# pcb_univ_3-8-0-x-rev3.net
KiCad netlist of a schematic drawn in EAGLE
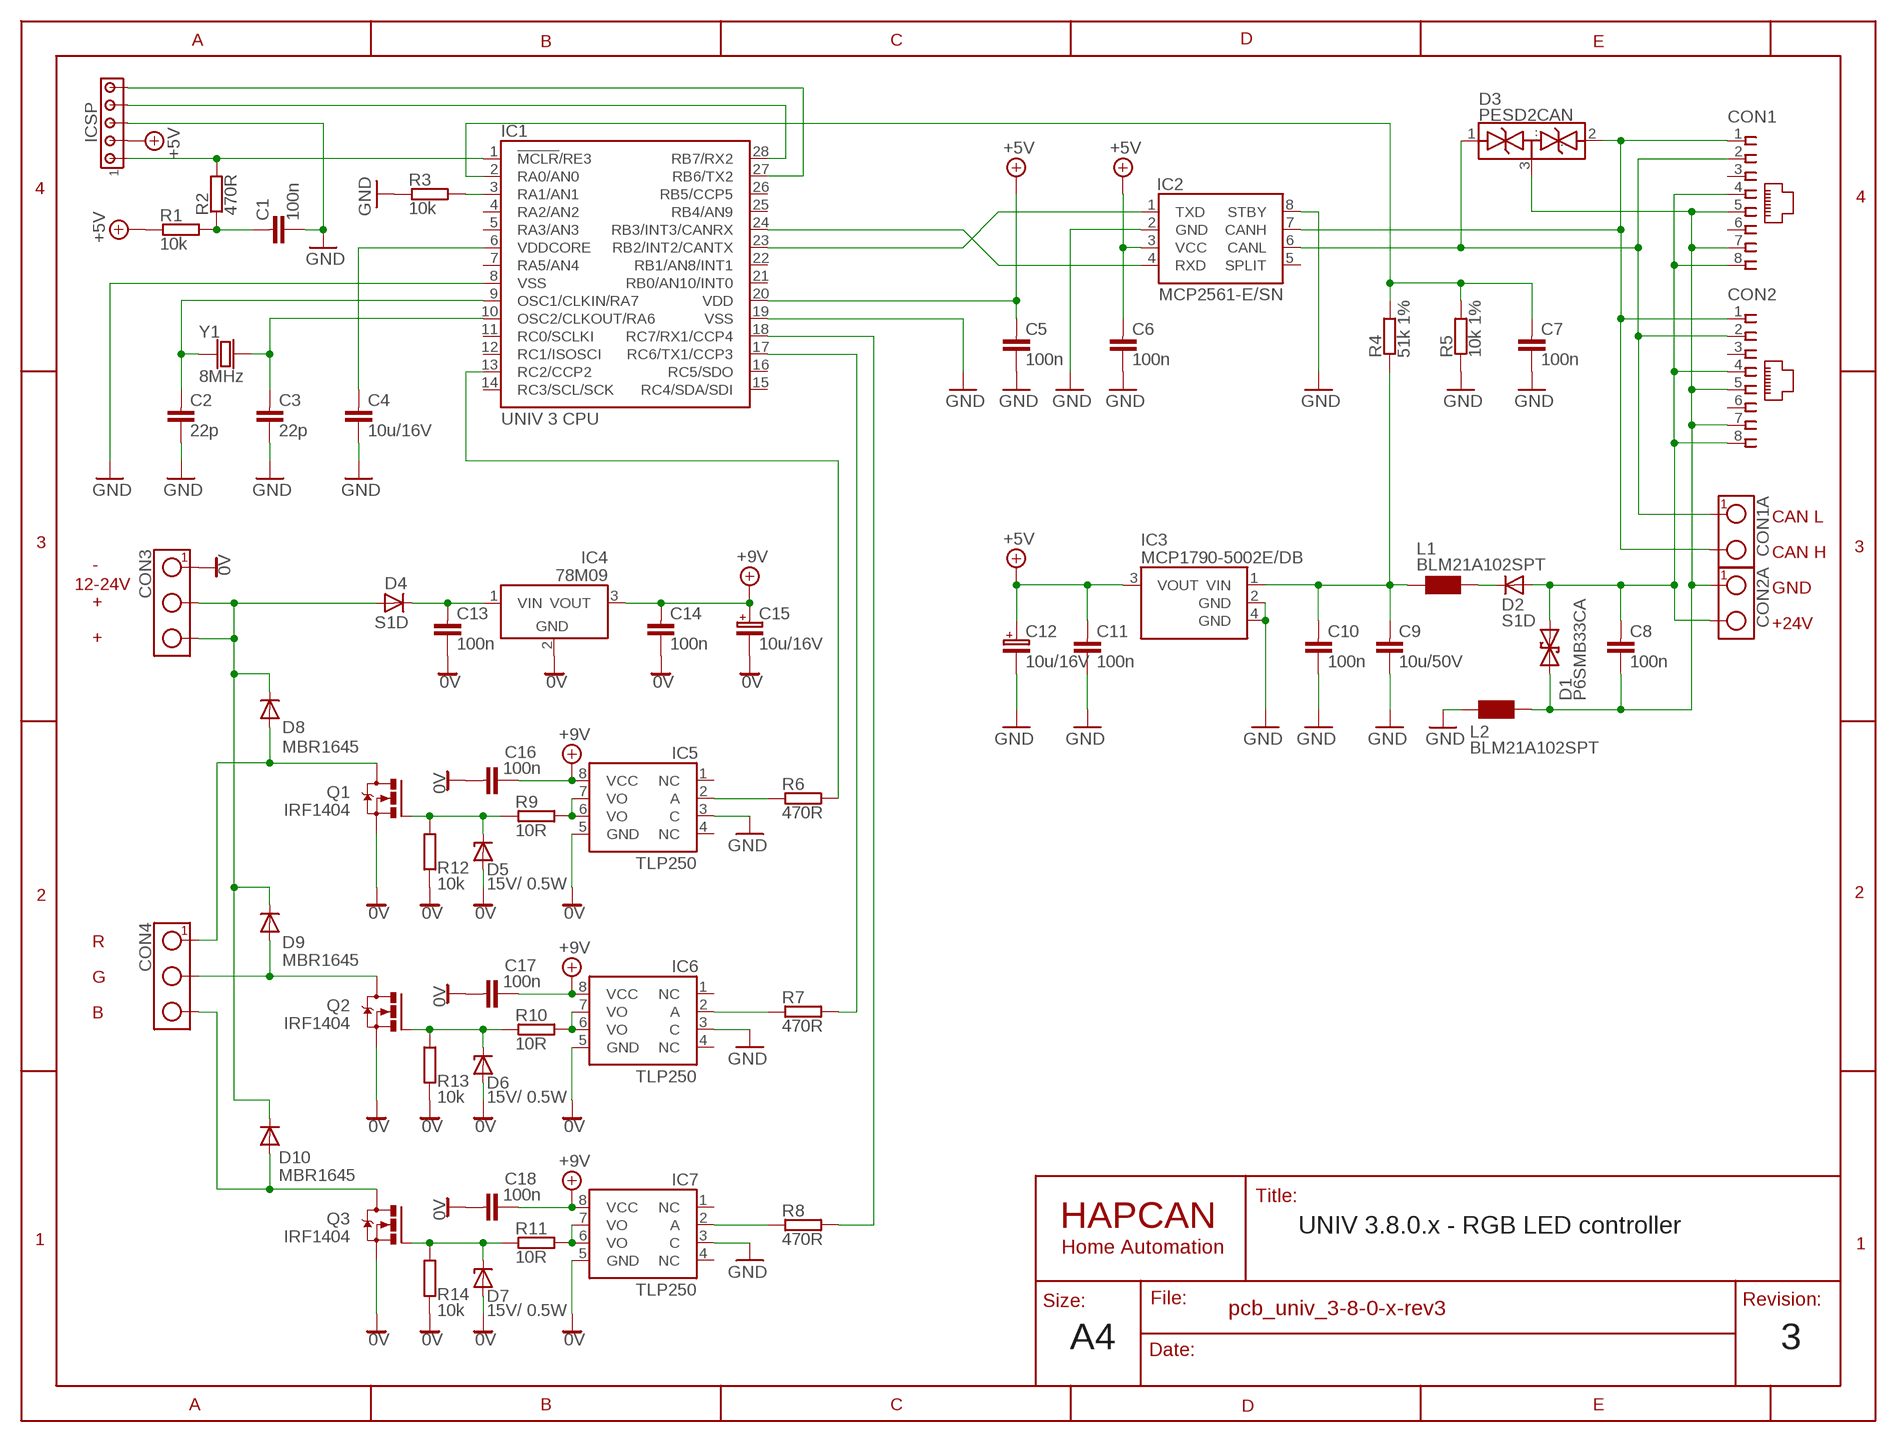
[diagram p0: schematic, sheet 1]

(export (version "E")
  (design (tool "Eeschema 10.0.6"))
  (components
    (comp (ref "C1")
      (value "100n")
      (footprint "eagle-import:0805")
      (libsource (lib "eagle-import") (part "CAPACITOR0805"))
    )
    (comp (ref "C2")
      (value "22p")
      (footprint "eagle-import:0805")
      (libsource (lib "eagle-import") (part "CAPACITOR0805"))
    )
    (comp (ref "C3")
      (value "22p")
      (footprint "eagle-import:0805")
      (libsource (lib "eagle-import") (part "CAPACITOR0805"))
    )
    (comp (ref "C4")
      (value "10u/16V")
      (footprint "eagle-import:0805")
      (libsource (lib "eagle-import") (part "CAPACITOR0805"))
    )
    (comp (ref "C5")
      (value "100n")
      (footprint "eagle-import:0805")
      (libsource (lib "eagle-import") (part "CAPACITOR0805"))
    )
    (comp (ref "C6")
      (value "100n")
      (footprint "eagle-import:0805")
      (libsource (lib "eagle-import") (part "CAPACITOR0805"))
    )
    (comp (ref "C7")
      (value "100n")
      (footprint "eagle-import:0805")
      (libsource (lib "eagle-import") (part "CAPACITOR0805"))
    )
    (comp (ref "C8")
      (value "100n")
      (footprint "eagle-import:0805")
      (libsource (lib "eagle-import") (part "CAPACITOR0805"))
    )
    (comp (ref "C9")
      (value "10u/50V")
      (footprint "eagle-import:1210")
      (libsource (lib "eagle-import") (part "CAPACITOR1210"))
    )
    (comp (ref "C10")
      (value "100n")
      (footprint "eagle-import:0805")
      (libsource (lib "eagle-import") (part "CAPACITOR0805"))
    )
    (comp (ref "C11")
      (value "100n")
      (footprint "eagle-import:0805")
      (libsource (lib "eagle-import") (part "CAPACITOR0805"))
    )
    (comp (ref "C12")
      (value "10u/16V")
      (footprint "eagle-import:SMC_B")
      (libsource (lib "eagle-import") (part "CAPACITOR-POLARIZED-SMC_B"))
    )
    (comp (ref "C13")
      (value "100n")
      (footprint "eagle-import:0805")
      (libsource (lib "eagle-import") (part "CAPACITOR0805"))
    )
    (comp (ref "C14")
      (value "100n")
      (footprint "eagle-import:0805")
      (libsource (lib "eagle-import") (part "CAPACITOR0805"))
    )
    (comp (ref "C15")
      (value "10u/16V")
      (footprint "eagle-import:SMC_B")
      (libsource (lib "eagle-import") (part "CAPACITOR-POLARIZED-SMC_B"))
    )
    (comp (ref "C16")
      (value "100n")
      (footprint "eagle-import:0805")
      (libsource (lib "eagle-import") (part "CAPACITOR0805"))
    )
    (comp (ref "C17")
      (value "100n")
      (footprint "eagle-import:0805")
      (libsource (lib "eagle-import") (part "CAPACITOR0805"))
    )
    (comp (ref "C18")
      (value "100n")
      (footprint "eagle-import:0805")
      (libsource (lib "eagle-import") (part "CAPACITOR0805"))
    )
    (comp (ref "CON1")
      (value "RJ45-SOCKET")
      (footprint "eagle-import:RJ45-PCB-SOCKET")
      (libsource (lib "eagle-import") (part "RJ45-SOCKET"))
    )
    (comp (ref "CON1A")
      (value "TERMINAL-2")
      (footprint "eagle-import:ARK2-5X10,5MM")
      (libsource (lib "eagle-import") (part "TERMINAL-2-5X10,5MM"))
    )
    (comp (ref "CON2")
      (value "RJ45-SOCKET")
      (footprint "eagle-import:RJ45-PCB-SOCKET")
      (libsource (lib "eagle-import") (part "RJ45-SOCKET"))
    )
    (comp (ref "CON2A")
      (value "TERMINAL-2")
      (footprint "eagle-import:ARK2-5X10,5MM")
      (libsource (lib "eagle-import") (part "TERMINAL-2-5X10,5MM"))
    )
    (comp (ref "CON3")
      (value "TERMINAL-3")
      (footprint "eagle-import:ARK3-5X10.5MM")
      (libsource (lib "eagle-import") (part "TERMINAL-3-5X10.5MM"))
    )
    (comp (ref "CON4")
      (value "TERMINAL-3")
      (footprint "eagle-import:ARK3-5X10.5MM")
      (libsource (lib "eagle-import") (part "TERMINAL-3-5X10.5MM"))
    )
    (comp (ref "D1")
      (value "P6SMB33CA")
      (footprint "eagle-import:DO-214_TRANSIL2")
      (libsource (lib "eagle-import") (part "DIODE_TRANSIL2"))
    )
    (comp (ref "D2")
      (value "S1D")
      (footprint "eagle-import:DO-214")
      (libsource (lib "eagle-import") (part "DIODE_DO-214"))
    )
    (comp (ref "D3")
      (value "PESD2CAN")
      (footprint "eagle-import:SOT-23")
      (libsource (lib "eagle-import") (part "PESD2CANSOT-23"))
    )
    (comp (ref "D4")
      (value "S1D")
      (footprint "eagle-import:DO-214")
      (libsource (lib "eagle-import") (part "DIODE_DO-214"))
    )
    (comp (ref "D5")
      (value "15V/ 0.5W")
      (footprint "eagle-import:SOD-80")
      (libsource (lib "eagle-import") (part "DIODE_ZENER_SOD-80"))
    )
    (comp (ref "D6")
      (value "15V/ 0.5W")
      (footprint "eagle-import:SOD-80")
      (libsource (lib "eagle-import") (part "DIODE_ZENER_SOD-80"))
    )
    (comp (ref "D7")
      (value "15V/ 0.5W")
      (footprint "eagle-import:SOD-80")
      (libsource (lib "eagle-import") (part "DIODE_ZENER_SOD-80"))
    )
    (comp (ref "D8")
      (value "MBR1645")
      (footprint "eagle-import:TO220V-2")
      (libsource (lib "eagle-import") (part "DIODE_TO220V"))
    )
    (comp (ref "D9")
      (value "MBR1645")
      (footprint "eagle-import:TO220V-2")
      (libsource (lib "eagle-import") (part "DIODE_TO220V"))
    )
    (comp (ref "D10")
      (value "MBR1645")
      (footprint "eagle-import:TO220V-2")
      (libsource (lib "eagle-import") (part "DIODE_TO220V"))
    )
    (comp (ref "IC1")
      (value "UNIV 3 CPU")
      (footprint "eagle-import:UNIV3CPU")
      (libsource (lib "eagle-import") (part "UNIV3CPU"))
    )
    (comp (ref "IC2")
      (value "MCP2561-E/SN")
      (footprint "eagle-import:SO-08")
      (libsource (lib "eagle-import") (part "MCP2561-E/SN"))
    )
    (comp (ref "IC3")
      (value "MCP1790-5002E/DB")
      (footprint "eagle-import:SOT-223")
      (libsource (lib "eagle-import") (part "MCP1790"))
    )
    (comp (ref "IC4")
      (value "78M09")
      (footprint "eagle-import:TO-252")
      (libsource (lib "eagle-import") (part "78XX_TO-252"))
    )
    (comp (ref "IC5")
      (value "TLP250")
      (footprint "eagle-import:DIL-08W")
      (libsource (lib "eagle-import") (part "TLP250_WIDE"))
    )
    (comp (ref "IC6")
      (value "TLP250")
      (footprint "eagle-import:DIL-08W")
      (libsource (lib "eagle-import") (part "TLP250_WIDE"))
    )
    (comp (ref "IC7")
      (value "TLP250")
      (footprint "eagle-import:DIL-08W")
      (libsource (lib "eagle-import") (part "TLP250_WIDE"))
    )
    (comp (ref "ICSP")
      (value "HEADER5")
      (footprint "eagle-import:SIP-5")
      (libsource (lib "eagle-import") (part "HEADER5"))
    )
    (comp (ref "L1")
      (value "BLM21A102SPT")
      (footprint "eagle-import:0805")
      (libsource (lib "eagle-import") (part "CHOKE0805"))
    )
    (comp (ref "L2")
      (value "BLM21A102SPT")
      (footprint "eagle-import:0805")
      (libsource (lib "eagle-import") (part "CHOKE0805"))
    )
    (comp (ref "Q1")
      (value "IRF1404")
      (footprint "eagle-import:TO220V")
      (libsource (lib "eagle-import") (part "TRANSISTOR_MOSFET_N_TO220V"))
    )
    (comp (ref "Q2")
      (value "IRF1404")
      (footprint "eagle-import:TO220V")
      (libsource (lib "eagle-import") (part "TRANSISTOR_MOSFET_N_TO220V"))
    )
    (comp (ref "Q3")
      (value "IRF1404")
      (footprint "eagle-import:TO220V")
      (libsource (lib "eagle-import") (part "TRANSISTOR_MOSFET_N_TO220V"))
    )
    (comp (ref "R1")
      (value "10k")
      (footprint "eagle-import:0805")
      (libsource (lib "eagle-import") (part "RESISTOR0805"))
    )
    (comp (ref "R2")
      (value "470R")
      (footprint "eagle-import:0805")
      (libsource (lib "eagle-import") (part "RESISTOR0805"))
    )
    (comp (ref "R3")
      (value "10k")
      (footprint "eagle-import:0805")
      (libsource (lib "eagle-import") (part "RESISTOR0805"))
    )
    (comp (ref "R4")
      (value "51k 1%")
      (footprint "eagle-import:0805")
      (libsource (lib "eagle-import") (part "RESISTOR0805"))
    )
    (comp (ref "R5")
      (value "10k 1%")
      (footprint "eagle-import:0805")
      (libsource (lib "eagle-import") (part "RESISTOR0805"))
    )
    (comp (ref "R6")
      (value "470R")
      (footprint "eagle-import:0805")
      (libsource (lib "eagle-import") (part "RESISTOR0805"))
    )
    (comp (ref "R7")
      (value "470R")
      (footprint "eagle-import:0805")
      (libsource (lib "eagle-import") (part "RESISTOR0805"))
    )
    (comp (ref "R8")
      (value "470R")
      (footprint "eagle-import:0805")
      (libsource (lib "eagle-import") (part "RESISTOR0805"))
    )
    (comp (ref "R9")
      (value "10R")
      (footprint "eagle-import:0805")
      (libsource (lib "eagle-import") (part "RESISTOR0805"))
    )
    (comp (ref "R10")
      (value "10R")
      (footprint "eagle-import:0805")
      (libsource (lib "eagle-import") (part "RESISTOR0805"))
    )
    (comp (ref "R11")
      (value "10R")
      (footprint "eagle-import:0805")
      (libsource (lib "eagle-import") (part "RESISTOR0805"))
    )
    (comp (ref "R12")
      (value "10k")
      (footprint "eagle-import:0805")
      (libsource (lib "eagle-import") (part "RESISTOR0805"))
    )
    (comp (ref "R13")
      (value "10k")
      (footprint "eagle-import:0805")
      (libsource (lib "eagle-import") (part "RESISTOR0805"))
    )
    (comp (ref "R14")
      (value "10k")
      (footprint "eagle-import:0805")
      (libsource (lib "eagle-import") (part "RESISTOR0805"))
    )
    (comp (ref "Y1")
      (value "8MHz")
      (footprint "eagle-import:CRYSTAL-HC49V")
      (libsource (lib "eagle-import") (part "CRYSTAL-HC49V"))
    )
  )
  (nets
    (net (code "1") (name "+5V") (class "Default")
      (node (ref "C11") (pin "1") (pinfunction "1_1") (pintype "passive"))
      (node (ref "C12") (pin "+") (pinfunction "1_+") (pintype "passive"))
      (node (ref "C5") (pin "1") (pinfunction "1_1") (pintype "passive"))
      (node (ref "C6") (pin "1") (pinfunction "1_1") (pintype "passive"))
      (node (ref "IC1") (pin "20") (pinfunction "VDD_20") (pintype "bidirectional"))
      (node (ref "IC2") (pin "3") (pinfunction "VCC_3") (pintype "bidirectional"))
      (node (ref "IC3") (pin "3") (pinfunction "VOUT_3") (pintype "bidirectional"))
      (node (ref "ICSP") (pin "2") (pinfunction "2_2") (pintype "passive"))
      (node (ref "R1") (pin "1") (pinfunction "1_1") (pintype "passive"))
    )
    (net (code "2") (name "+9V") (class "Default")
      (node (ref "C14") (pin "1") (pinfunction "1_1") (pintype "passive"))
      (node (ref "C15") (pin "+") (pinfunction "1_+") (pintype "passive"))
      (node (ref "C16") (pin "2") (pinfunction "2_2") (pintype "passive"))
      (node (ref "C17") (pin "2") (pinfunction "2_2") (pintype "passive"))
      (node (ref "C18") (pin "2") (pinfunction "2_2") (pintype "passive"))
      (node (ref "IC4") (pin "3") (pinfunction "VOUT_3") (pintype "bidirectional"))
      (node (ref "IC5") (pin "8") (pinfunction "VCC_8") (pintype "bidirectional"))
      (node (ref "IC6") (pin "8") (pinfunction "VCC_8") (pintype "bidirectional"))
      (node (ref "IC7") (pin "8") (pinfunction "VCC_8") (pintype "bidirectional"))
    )
    (net (code "3") (name "0V") (class "Default")
      (node (ref "C13") (pin "2") (pinfunction "2_2") (pintype "passive"))
      (node (ref "C14") (pin "2") (pinfunction "2_2") (pintype "passive"))
      (node (ref "C15") (pin "-") (pinfunction "2_-") (pintype "passive"))
      (node (ref "C16") (pin "1") (pinfunction "1_1") (pintype "passive"))
      (node (ref "C17") (pin "1") (pinfunction "1_1") (pintype "passive"))
      (node (ref "C18") (pin "1") (pinfunction "1_1") (pintype "passive"))
      (node (ref "CON3") (pin "1") (pinfunction "1_1") (pintype "passive"))
      (node (ref "D5") (pin "A") (pinfunction "A_A") (pintype "passive"))
      (node (ref "D6") (pin "A") (pinfunction "A_A") (pintype "passive"))
      (node (ref "D7") (pin "A") (pinfunction "A_A") (pintype "passive"))
      (node (ref "IC4") (pin "2") (pinfunction "GND_2") (pintype "bidirectional"))
      (node (ref "IC5") (pin "5") (pinfunction "GND_5") (pintype "bidirectional"))
      (node (ref "IC6") (pin "5") (pinfunction "GND_5") (pintype "bidirectional"))
      (node (ref "IC7") (pin "5") (pinfunction "GND_5") (pintype "bidirectional"))
      (node (ref "Q1") (pin "3") (pinfunction "S_3") (pintype "passive"))
      (node (ref "Q2") (pin "3") (pinfunction "S_3") (pintype "passive"))
      (node (ref "Q3") (pin "3") (pinfunction "S_3") (pintype "passive"))
      (node (ref "R12") (pin "1") (pinfunction "1_1") (pintype "passive"))
      (node (ref "R13") (pin "1") (pinfunction "1_1") (pintype "passive"))
      (node (ref "R14") (pin "1") (pinfunction "1_1") (pintype "passive"))
    )
    (net (code "4") (name "GND") (class "Default")
      (node (ref "C1") (pin "2") (pinfunction "2_2") (pintype "passive"))
      (node (ref "C10") (pin "2") (pinfunction "2_2") (pintype "passive"))
      (node (ref "C11") (pin "2") (pinfunction "2_2") (pintype "passive"))
      (node (ref "C12") (pin "-") (pinfunction "2_-") (pintype "passive"))
      (node (ref "C2") (pin "2") (pinfunction "2_2") (pintype "passive"))
      (node (ref "C3") (pin "2") (pinfunction "2_2") (pintype "passive"))
      (node (ref "C4") (pin "2") (pinfunction "2_2") (pintype "passive"))
      (node (ref "C5") (pin "2") (pinfunction "2_2") (pintype "passive"))
      (node (ref "C6") (pin "2") (pinfunction "2_2") (pintype "passive"))
      (node (ref "C7") (pin "2") (pinfunction "2_2") (pintype "passive"))
      (node (ref "C9") (pin "2") (pinfunction "2_2") (pintype "passive"))
      (node (ref "IC1") (pin "19") (pinfunction "VSS_19") (pintype "bidirectional"))
      (node (ref "IC1") (pin "8") (pinfunction "VSS_8") (pintype "bidirectional"))
      (node (ref "IC2") (pin "2") (pinfunction "GND_2") (pintype "bidirectional"))
      (node (ref "IC2") (pin "8") (pinfunction "STBY_8") (pintype "bidirectional"))
      (node (ref "IC3") (pin "2") (pinfunction "GND_2") (pintype "bidirectional"))
      (node (ref "IC3") (pin "4") (pinfunction "GND_4") (pintype "bidirectional"))
      (node (ref "IC5") (pin "3") (pinfunction "C_3") (pintype "bidirectional"))
      (node (ref "IC6") (pin "3") (pinfunction "C_3") (pintype "bidirectional"))
      (node (ref "IC7") (pin "3") (pinfunction "C_3") (pintype "bidirectional"))
      (node (ref "ICSP") (pin "3") (pinfunction "3_3") (pintype "passive"))
      (node (ref "L2") (pin "1") (pinfunction "1_1") (pintype "passive"))
      (node (ref "R3") (pin "1") (pinfunction "1_1") (pintype "passive"))
      (node (ref "R5") (pin "1") (pinfunction "1_1") (pintype "passive"))
    )
    (net (code "5") (name "Net-(C1-Pad1)") (class "Default")
      (node (ref "C1") (pin "1") (pinfunction "1_1") (pintype "passive"))
      (node (ref "R1") (pin "2") (pinfunction "2_2") (pintype "passive"))
      (node (ref "R2") (pin "1") (pinfunction "1_1") (pintype "passive"))
    )
    (net (code "6") (name "Net-(D1-1)") (class "Default")
      (node (ref "C8") (pin "2") (pinfunction "2_2") (pintype "passive"))
      (node (ref "CON1") (pin "5") (pinfunction "5_5") (pintype "passive"))
      (node (ref "CON1") (pin "7") (pinfunction "7_7") (pintype "passive"))
      (node (ref "CON2") (pin "5") (pinfunction "5_5") (pintype "passive"))
      (node (ref "CON2") (pin "7") (pinfunction "7_7") (pintype "passive"))
      (node (ref "CON2A") (pin "1") (pinfunction "1_1") (pintype "passive"))
      (node (ref "D1") (pin "A") (pinfunction "1_A") (pintype "passive"))
      (node (ref "D3") (pin "3") (pinfunction "..._3") (pintype "bidirectional"))
      (node (ref "L2") (pin "2") (pinfunction "2_2") (pintype "passive"))
    )
    (net (code "7") (name "Net-(D1-2)") (class "Default")
      (node (ref "C8") (pin "1") (pinfunction "1_1") (pintype "passive"))
      (node (ref "CON1") (pin "4") (pinfunction "4_4") (pintype "passive"))
      (node (ref "CON1") (pin "8") (pinfunction "8_8") (pintype "passive"))
      (node (ref "CON2") (pin "4") (pinfunction "4_4") (pintype "passive"))
      (node (ref "CON2") (pin "8") (pinfunction "8_8") (pintype "passive"))
      (node (ref "CON2A") (pin "2") (pinfunction "2_2") (pintype "passive"))
      (node (ref "D1") (pin "C") (pinfunction "2_C") (pintype "passive"))
      (node (ref "D2") (pin "A") (pinfunction "A_A") (pintype "passive"))
    )
    (net (code "8") (name "Net-(D2-PadC)") (class "Default")
      (node (ref "D2") (pin "C") (pinfunction "C_C") (pintype "passive"))
      (node (ref "L1") (pin "2") (pinfunction "2_2") (pintype "passive"))
    )
    (net (code "9") (name "Net-(D3-.)") (class "Default")
      (node (ref "CON1") (pin "2") (pinfunction "2_2") (pintype "passive"))
      (node (ref "CON1A") (pin "1") (pinfunction "1_1") (pintype "passive"))
      (node (ref "CON2") (pin "2") (pinfunction "2_2") (pintype "passive"))
      (node (ref "D3") (pin "1") (pinfunction "._1") (pintype "bidirectional"))
      (node (ref "IC2") (pin "6") (pinfunction "CANL_6") (pintype "bidirectional"))
    )
    (net (code "10") (name "Net-(D3-..)") (class "Default")
      (node (ref "CON1") (pin "1") (pinfunction "1_1") (pintype "passive"))
      (node (ref "CON1A") (pin "2") (pinfunction "2_2") (pintype "passive"))
      (node (ref "CON2") (pin "1") (pinfunction "1_1") (pintype "passive"))
      (node (ref "D3") (pin "2") (pinfunction ".._2") (pintype "bidirectional"))
      (node (ref "IC2") (pin "7") (pinfunction "CANH_7") (pintype "bidirectional"))
    )
    (net (code "11") (name "Net-(D8-A)") (class "Default")
      (node (ref "CON4") (pin "1") (pinfunction "1_1") (pintype "passive"))
      (node (ref "D8") (pin "3") (pinfunction "A_3") (pintype "passive"))
      (node (ref "Q1") (pin "2") (pinfunction "D_2") (pintype "passive"))
    )
    (net (code "12") (name "Net-(D9-A)") (class "Default")
      (node (ref "CON4") (pin "2") (pinfunction "2_2") (pintype "passive"))
      (node (ref "D9") (pin "3") (pinfunction "A_3") (pintype "passive"))
      (node (ref "Q2") (pin "2") (pinfunction "D_2") (pintype "passive"))
    )
    (net (code "13") (name "Net-(D10-A)") (class "Default")
      (node (ref "CON4") (pin "3") (pinfunction "3_3") (pintype "passive"))
      (node (ref "D10") (pin "3") (pinfunction "A_3") (pintype "passive"))
      (node (ref "Q3") (pin "2") (pinfunction "D_2") (pintype "passive"))
    )
    (net (code "14") (name "Net-(D10-C)") (class "Default")
      (node (ref "CON3") (pin "2") (pinfunction "2_2") (pintype "passive"))
      (node (ref "CON3") (pin "3") (pinfunction "3_3") (pintype "passive"))
      (node (ref "D10") (pin "1") (pinfunction "C_1") (pintype "passive"))
      (node (ref "D4") (pin "A") (pinfunction "A_A") (pintype "passive"))
      (node (ref "D8") (pin "1") (pinfunction "C_1") (pintype "passive"))
      (node (ref "D9") (pin "1") (pinfunction "C_1") (pintype "passive"))
    )
    (net (code "15") (name "Net-(IC1-OSC1{slash}CLKIN{slash}RA7)") (class "Default")
      (node (ref "C2") (pin "1") (pinfunction "1_1") (pintype "passive"))
      (node (ref "IC1") (pin "9") (pinfunction "OSC1/CLKIN/RA7_9") (pintype "bidirectional"))
      (node (ref "Y1") (pin "1") (pinfunction "1_1") (pintype "passive"))
    )
    (net (code "16") (name "Net-(IC1-OSC2{slash}CLKOUT{slash}RA6)") (class "Default")
      (node (ref "C3") (pin "1") (pinfunction "1_1") (pintype "passive"))
      (node (ref "IC1") (pin "10") (pinfunction "OSC2/CLKOUT/RA6_10") (pintype "bidirectional"))
      (node (ref "Y1") (pin "2") (pinfunction "2_2") (pintype "passive"))
    )
    (net (code "17") (name "Net-(IC1-RA0{slash}AN0)") (class "Default")
      (node (ref "C7") (pin "1") (pinfunction "1_1") (pintype "passive"))
      (node (ref "IC1") (pin "2") (pinfunction "RA0/AN0_2") (pintype "bidirectional"))
      (node (ref "R4") (pin "2") (pinfunction "2_2") (pintype "passive"))
      (node (ref "R5") (pin "2") (pinfunction "2_2") (pintype "passive"))
    )
    (net (code "18") (name "Net-(IC1-RA1{slash}AN1)") (class "Default")
      (node (ref "IC1") (pin "3") (pinfunction "RA1/AN1_3") (pintype "bidirectional"))
      (node (ref "R3") (pin "2") (pinfunction "2_2") (pintype "passive"))
    )
    (net (code "19") (name "Net-(IC1-RB2{slash}INT2{slash}CANTX)") (class "Default")
      (node (ref "IC1") (pin "23") (pinfunction "RB2/INT2/CANTX_23") (pintype "bidirectional"))
      (node (ref "IC2") (pin "1") (pinfunction "TXD_1") (pintype "bidirectional"))
    )
    (net (code "20") (name "Net-(IC1-RB3{slash}INT3{slash}CANRX)") (class "Default")
      (node (ref "IC1") (pin "24") (pinfunction "RB3/INT3/CANRX_24") (pintype "bidirectional"))
      (node (ref "IC2") (pin "4") (pinfunction "RXD_4") (pintype "bidirectional"))
    )
    (net (code "21") (name "Net-(IC1-RB6{slash}TX2)") (class "Default")
      (node (ref "IC1") (pin "27") (pinfunction "RB6/TX2_27") (pintype "bidirectional"))
      (node (ref "ICSP") (pin "5") (pinfunction "5_5") (pintype "passive"))
    )
    (net (code "22") (name "Net-(IC1-RB7{slash}RX2)") (class "Default")
      (node (ref "IC1") (pin "28") (pinfunction "RB7/RX2_28") (pintype "bidirectional"))
      (node (ref "ICSP") (pin "4") (pinfunction "4_4") (pintype "passive"))
    )
    (net (code "23") (name "Net-(IC1-RC2{slash}CCP2)") (class "Default")
      (node (ref "IC1") (pin "13") (pinfunction "RC2/CCP2_13") (pintype "bidirectional"))
      (node (ref "R6") (pin "2") (pinfunction "2_2") (pintype "passive"))
    )
    (net (code "24") (name "Net-(IC1-RC6{slash}TX1{slash}CCP3)") (class "Default")
      (node (ref "IC1") (pin "17") (pinfunction "RC6/TX1/CCP3_17") (pintype "bidirectional"))
      (node (ref "R7") (pin "2") (pinfunction "2_2") (pintype "passive"))
    )
    (net (code "25") (name "Net-(IC1-RC7{slash}RX1{slash}CCP4)") (class "Default")
      (node (ref "IC1") (pin "18") (pinfunction "RC7/RX1/CCP4_18") (pintype "bidirectional"))
      (node (ref "R8") (pin "2") (pinfunction "2_2") (pintype "passive"))
    )
    (net (code "26") (name "Net-(IC1-VDDCORE)") (class "Default")
      (node (ref "C4") (pin "1") (pinfunction "1_1") (pintype "passive"))
      (node (ref "IC1") (pin "6") (pinfunction "VDDCORE_6") (pintype "bidirectional"))
    )
    (net (code "27") (name "Net-(IC1-~{MCLR}{slash}RE3)") (class "Default")
      (node (ref "IC1") (pin "1") (pinfunction "~{MCLR}/RE3_1") (pintype "bidirectional"))
      (node (ref "ICSP") (pin "1") (pinfunction "1_1") (pintype "passive"))
      (node (ref "R2") (pin "2") (pinfunction "2_2") (pintype "passive"))
    )
    (net (code "28") (name "Net-(IC3-VIN)") (class "Default")
      (node (ref "C10") (pin "1") (pinfunction "1_1") (pintype "passive"))
      (node (ref "C9") (pin "1") (pinfunction "1_1") (pintype "passive"))
      (node (ref "IC3") (pin "1") (pinfunction "VIN_1") (pintype "bidirectional"))
      (node (ref "L1") (pin "1") (pinfunction "1_1") (pintype "passive"))
      (node (ref "R4") (pin "1") (pinfunction "1_1") (pintype "passive"))
    )
    (net (code "29") (name "Net-(IC4-VIN)") (class "Default")
      (node (ref "C13") (pin "1") (pinfunction "1_1") (pintype "passive"))
      (node (ref "D4") (pin "C") (pinfunction "C_C") (pintype "passive"))
      (node (ref "IC4") (pin "1") (pinfunction "VIN_1") (pintype "bidirectional"))
    )
    (net (code "30") (name "Net-(IC5-A)") (class "Default")
      (node (ref "IC5") (pin "2") (pinfunction "A_2") (pintype "bidirectional"))
      (node (ref "R6") (pin "1") (pinfunction "1_1") (pintype "passive"))
    )
    (net (code "31") (name "Net-(IC5-VO-Pad6)") (class "Default")
      (node (ref "IC5") (pin "6") (pinfunction "VO_6") (pintype "bidirectional"))
      (node (ref "IC5") (pin "7") (pinfunction "VO_7") (pintype "bidirectional"))
      (node (ref "R9") (pin "2") (pinfunction "2_2") (pintype "passive"))
    )
    (net (code "32") (name "Net-(IC6-A)") (class "Default")
      (node (ref "IC6") (pin "2") (pinfunction "A_2") (pintype "bidirectional"))
      (node (ref "R7") (pin "1") (pinfunction "1_1") (pintype "passive"))
    )
    (net (code "33") (name "Net-(IC6-VO-Pad6)") (class "Default")
      (node (ref "IC6") (pin "6") (pinfunction "VO_6") (pintype "bidirectional"))
      (node (ref "IC6") (pin "7") (pinfunction "VO_7") (pintype "bidirectional"))
      (node (ref "R10") (pin "2") (pinfunction "2_2") (pintype "passive"))
    )
    (net (code "34") (name "Net-(IC7-A)") (class "Default")
      (node (ref "IC7") (pin "2") (pinfunction "A_2") (pintype "bidirectional"))
      (node (ref "R8") (pin "1") (pinfunction "1_1") (pintype "passive"))
    )
    (net (code "35") (name "Net-(IC7-VO-Pad6)") (class "Default")
      (node (ref "IC7") (pin "6") (pinfunction "VO_6") (pintype "bidirectional"))
      (node (ref "IC7") (pin "7") (pinfunction "VO_7") (pintype "bidirectional"))
      (node (ref "R11") (pin "2") (pinfunction "2_2") (pintype "passive"))
    )
    (net (code "36") (name "Net-(Q1-G)") (class "Default")
      (node (ref "D5") (pin "C") (pinfunction "C_C") (pintype "passive"))
      (node (ref "Q1") (pin "1") (pinfunction "G_1") (pintype "passive"))
      (node (ref "R12") (pin "2") (pinfunction "2_2") (pintype "passive"))
      (node (ref "R9") (pin "1") (pinfunction "1_1") (pintype "passive"))
    )
    (net (code "37") (name "Net-(Q2-G)") (class "Default")
      (node (ref "D6") (pin "C") (pinfunction "C_C") (pintype "passive"))
      (node (ref "Q2") (pin "1") (pinfunction "G_1") (pintype "passive"))
      (node (ref "R10") (pin "1") (pinfunction "1_1") (pintype "passive"))
      (node (ref "R13") (pin "2") (pinfunction "2_2") (pintype "passive"))
    )
    (net (code "38") (name "Net-(Q3-G)") (class "Default")
      (node (ref "D7") (pin "C") (pinfunction "C_C") (pintype "passive"))
      (node (ref "Q3") (pin "1") (pinfunction "G_1") (pintype "passive"))
      (node (ref "R11") (pin "1") (pinfunction "1_1") (pintype "passive"))
      (node (ref "R14") (pin "2") (pinfunction "2_2") (pintype "passive"))
    )
    (net (code "39") (name "unconnected-(CON1-Pad3)") (class "Default")
      (node (ref "CON1") (pin "3") (pinfunction "3_3") (pintype "passive"))
    )
    (net (code "40") (name "unconnected-(CON1-Pad6)") (class "Default")
      (node (ref "CON1") (pin "6") (pinfunction "6_6") (pintype "passive"))
    )
    (net (code "41") (name "unconnected-(CON2-Pad3)") (class "Default")
      (node (ref "CON2") (pin "3") (pinfunction "3_3") (pintype "passive"))
    )
    (net (code "42") (name "unconnected-(CON2-Pad6)") (class "Default")
      (node (ref "CON2") (pin "6") (pinfunction "6_6") (pintype "passive"))
    )
    (net (code "43") (name "unconnected-(IC1-RA2{slash}AN2-Pad4)") (class "Default")
      (node (ref "IC1") (pin "4") (pinfunction "RA2/AN2_4") (pintype "bidirectional"))
    )
    (net (code "44") (name "unconnected-(IC1-RA3{slash}AN3-Pad5)") (class "Default")
      (node (ref "IC1") (pin "5") (pinfunction "RA3/AN3_5") (pintype "bidirectional"))
    )
    (net (code "45") (name "unconnected-(IC1-RA5{slash}AN4-Pad7)") (class "Default")
      (node (ref "IC1") (pin "7") (pinfunction "RA5/AN4_7") (pintype "bidirectional"))
    )
    (net (code "46") (name "unconnected-(IC1-RB0{slash}AN10{slash}INT0-Pad21)") (class "Default")
      (node (ref "IC1") (pin "21") (pinfunction "RB0/AN10/INT0_21") (pintype "bidirectional"))
    )
    (net (code "47") (name "unconnected-(IC1-RB1{slash}AN8{slash}INT1-Pad22)") (class "Default")
      (node (ref "IC1") (pin "22") (pinfunction "RB1/AN8/INT1_22") (pintype "bidirectional"))
    )
    (net (code "48") (name "unconnected-(IC1-RB4{slash}AN9-Pad25)") (class "Default")
      (node (ref "IC1") (pin "25") (pinfunction "RB4/AN9_25") (pintype "bidirectional"))
    )
    (net (code "49") (name "unconnected-(IC1-RB5{slash}CCP5-Pad26)") (class "Default")
      (node (ref "IC1") (pin "26") (pinfunction "RB5/CCP5_26") (pintype "bidirectional"))
    )
    (net (code "50") (name "unconnected-(IC1-RC0{slash}SCLKI-Pad11)") (class "Default")
      (node (ref "IC1") (pin "11") (pinfunction "RC0/SCLKI_11") (pintype "bidirectional"))
    )
    (net (code "51") (name "unconnected-(IC1-RC1{slash}ISOSCI-Pad12)") (class "Default")
      (node (ref "IC1") (pin "12") (pinfunction "RC1/ISOSCI_12") (pintype "bidirectional"))
    )
    (net (code "52") (name "unconnected-(IC1-RC3{slash}SCL{slash}SCK-Pad14)") (class "Default")
      (node (ref "IC1") (pin "14") (pinfunction "RC3/SCL/SCK_14") (pintype "bidirectional"))
    )
    (net (code "53") (name "unconnected-(IC1-RC4{slash}SDA{slash}SDI-Pad15)") (class "Default")
      (node (ref "IC1") (pin "15") (pinfunction "RC4/SDA/SDI_15") (pintype "bidirectional"))
    )
    (net (code "54") (name "unconnected-(IC1-RC5{slash}SDO-Pad16)") (class "Default")
      (node (ref "IC1") (pin "16") (pinfunction "RC5/SDO_16") (pintype "bidirectional"))
    )
    (net (code "55") (name "unconnected-(IC2-SPLIT-Pad5)") (class "Default")
      (node (ref "IC2") (pin "5") (pinfunction "SPLIT_5") (pintype "bidirectional"))
    )
    (net (code "56") (name "unconnected-(IC5-NC-Pad1)") (class "Default")
      (node (ref "IC5") (pin "1") (pinfunction "NC_1") (pintype "bidirectional"))
    )
    (net (code "57") (name "unconnected-(IC5-NC-Pad4)") (class "Default")
      (node (ref "IC5") (pin "4") (pinfunction "NC_4") (pintype "bidirectional"))
    )
    (net (code "58") (name "unconnected-(IC6-NC-Pad1)") (class "Default")
      (node (ref "IC6") (pin "1") (pinfunction "NC_1") (pintype "bidirectional"))
    )
    (net (code "59") (name "unconnected-(IC6-NC-Pad4)") (class "Default")
      (node (ref "IC6") (pin "4") (pinfunction "NC_4") (pintype "bidirectional"))
    )
    (net (code "60") (name "unconnected-(IC7-NC-Pad1)") (class "Default")
      (node (ref "IC7") (pin "1") (pinfunction "NC_1") (pintype "bidirectional"))
    )
    (net (code "61") (name "unconnected-(IC7-NC-Pad4)") (class "Default")
      (node (ref "IC7") (pin "4") (pinfunction "NC_4") (pintype "bidirectional"))
    )
  )
)
